# QCopterFC_PWR_Sch.net
KiCad netlist of a schematic drawn in Altium Designer
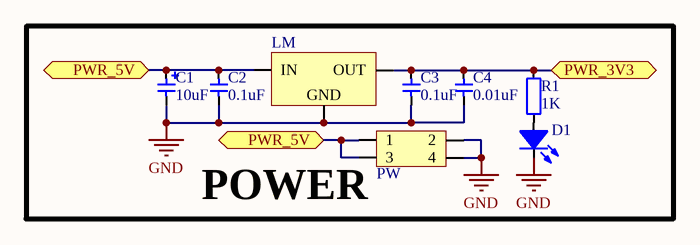
[diagram p0: QCopterFC_PWR_Sch.SchDoc]

(export (version "E")
  (design (tool "Eeschema 10.0.6"))
  (components
    (comp (ref "C1")
      (value "10uF")
      (footprint "PCB_Passive:CAP_TAN_B1210")
      (description "Capacitor")
      (fields (field (name "Comment") "Cap_Tan_1210"))
      (libsource (lib "SCH_Passive") (part "Cap_Tan_1210"))
    )
    (comp (ref "C2")
      (value "0.1uF")
      (footprint "PCB_Passive:CAP_0603")
      (description "Capacitor")
      (fields (field (name "Comment") "Cap_0603"))
      (libsource (lib "SCH_Passive") (part "Cap_0603"))
    )
    (comp (ref "C3")
      (value "0.1uF")
      (footprint "PCB_Passive:CAP_0603")
      (description "Capacitor")
      (fields (field (name "Comment") "Cap_0603"))
      (libsource (lib "SCH_Passive") (part "Cap_0603"))
    )
    (comp (ref "C4")
      (value "0.01uF")
      (footprint "PCB_Passive:CAP_0603")
      (description "Capacitor")
      (fields (field (name "Comment") "Cap_0603"))
      (libsource (lib "SCH_Passive") (part "Cap_0603"))
    )
    (comp (ref "D1")
      (value "LED_0603")
      (footprint "PCB_Active:LED_0603_WHITE")
      (description "LED")
      (libsource (lib "SCH_Active") (part "LED_0603"))
    )
    (comp (ref "LM")
      (value "LM1117")
      (footprint "PCB_IC:SOT223")
      (description "Power")
      (libsource (lib "SCH_IC") (part "LM1117"))
    )
    (comp (ref "PW")
      (value "HDR2X2_90_2.54")
      (footprint "PCB_Connector:HDR2X2_90_2.54")
      (description "Header")
      (libsource (lib "SCH_Connector") (part "HDR2X2_90_2.54"))
    )
    (comp (ref "R1")
      (value "1K")
      (footprint "PCB_Passive:RES_0603")
      (description "Resistor")
      (fields (field (name "Comment") "Res_0603"))
      (libsource (lib "SCH_Passive") (part "Res_0603"))
    )
  )
  (nets
    (net (code "1") (name "/PWR_3V3") (class "Default")
      (node (ref "C3") (pin "2") (pinfunction "2_2") (pintype "passive"))
      (node (ref "C4") (pin "2") (pinfunction "2_2") (pintype "passive"))
      (node (ref "LM") (pin "2") (pinfunction "OUT_2") (pintype "power_in"))
      (node (ref "R1") (pin "2") (pinfunction "2_2") (pintype "passive"))
    )
    (net (code "2") (name "/PWR_5V") (class "Default")
      (node (ref "C1") (pin "1") (pinfunction "1_1") (pintype "passive"))
      (node (ref "C2") (pin "2") (pinfunction "2_2") (pintype "passive"))
      (node (ref "LM") (pin "3") (pinfunction "IN_3") (pintype "power_in"))
      (node (ref "PW") (pin "1") (pinfunction "1_1") (pintype "passive"))
      (node (ref "PW") (pin "3") (pinfunction "3_3") (pintype "passive"))
    )
    (net (code "3") (name "GND") (class "Default")
      (node (ref "C1") (pin "2") (pinfunction "2_2") (pintype "passive"))
      (node (ref "C2") (pin "1") (pinfunction "1_1") (pintype "passive"))
      (node (ref "C3") (pin "1") (pinfunction "1_1") (pintype "passive"))
      (node (ref "C4") (pin "1") (pinfunction "1_1") (pintype "passive"))
      (node (ref "D1") (pin "2") (pinfunction "K_2") (pintype "passive"))
      (node (ref "LM") (pin "1") (pinfunction "GND_1") (pintype "power_in"))
      (node (ref "PW") (pin "2") (pinfunction "2_2") (pintype "passive"))
      (node (ref "PW") (pin "4") (pinfunction "4_4") (pintype "passive"))
    )
    (net (code "4") (name "Net-(D1-A)") (class "Default")
      (node (ref "D1") (pin "1") (pinfunction "A_1") (pintype "passive"))
      (node (ref "R1") (pin "1") (pinfunction "1_1") (pintype "passive"))
    )
  )
)
